# PIC.net
KiCad netlist of a schematic drawn in Altium Designer
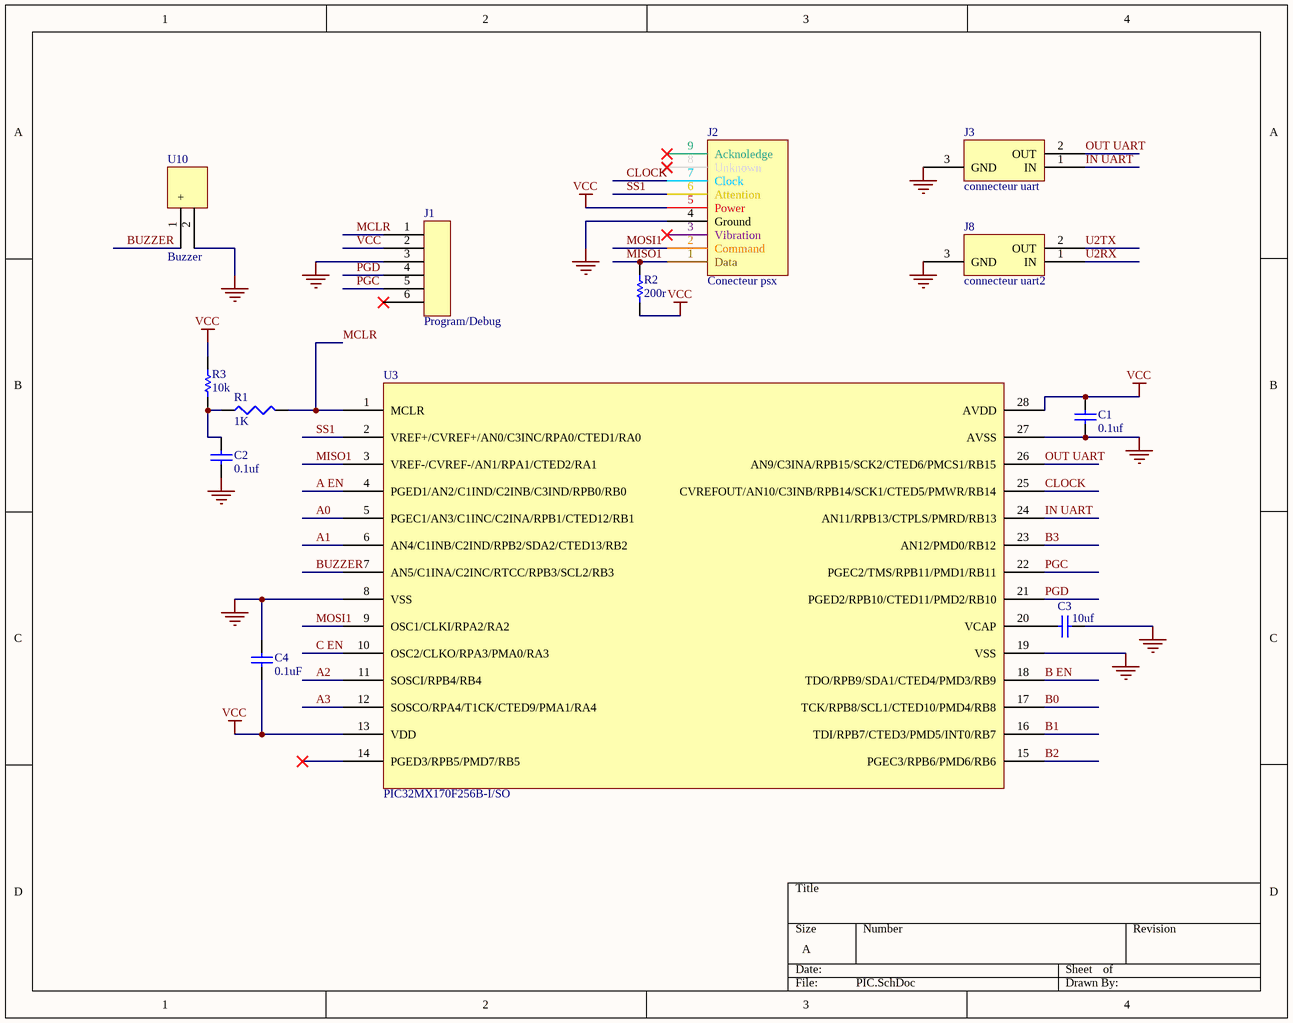
[diagram p0: PIC.SchDoc]

(export (version "E")
  (design (tool "Eeschema 10.0.6"))
  (components
    (comp (ref "C1")
      (value "0.1uf")
      (footprint "CAPC1608X09N")
      (description "Capacitor")
      (fields (field (name "PUBLISHER") "Altium Limited"))
      (libsource (lib "Miscellaneous Devices") (part "Cap"))
    )
    (comp (ref "C2")
      (value "0.1uf")
      (footprint "CAPC1608X09N")
      (description "Capacitor")
      (fields (field (name "PUBLISHER") "Altium Limited"))
      (libsource (lib "Miscellaneous Devices") (part "Cap"))
    )
    (comp (ref "C3")
      (value "10uf")
      (footprint "CAPC1608X09N")
      (description "Capacitor")
      (fields (field (name "PUBLISHER") "Altium Limited"))
      (libsource (lib "Miscellaneous Devices") (part "Cap"))
    )
    (comp (ref "C4")
      (value "0.1uF")
      (footprint "CAPC1608X09N")
      (description "Capacitor")
      (fields (field (name "PUBLISHER") "Altium Limited"))
      (libsource (lib "Miscellaneous Devices") (part "Cap"))
    )
    (comp (ref "J1")
      (value "Program/Debug")
      (footprint "Debug")
      (libsource (lib "TP-II_PD") (part "Component_1"))
    )
    (comp (ref "J2")
      (value "Conecteur psx")
      (footprint "PCBComponent_1")
      (libsource (lib "PS2_PAD") (part "Component_1"))
    )
    (comp (ref "J3")
      (value "connecteur uart")
      (footprint "uart")
      (libsource (lib "lib_protoboard") (part "connecteur uart"))
    )
    (comp (ref "J8")
      (value "connecteur uart2")
      (footprint "uart")
      (libsource (lib "lib_protoboard") (part "connecteur uart"))
    )
    (comp (ref "R1")
      (value "1K")
      (footprint "CAPC1608X09N")
      (description "Resistor")
      (fields (field (name "PUBLISHER") "Altium Limited"))
      (libsource (lib "Miscellaneous Devices") (part "Res3"))
    )
    (comp (ref "R2")
      (value "200r")
      (footprint "CAPC1608X09N")
      (description "Resistor")
      (fields (field (name "PUBLISHER") "Altium Limited"))
      (libsource (lib "Miscellaneous Devices") (part "Res1"))
    )
    (comp (ref "R3")
      (value "10k")
      (footprint "CAPC1608X09N")
      (description "Resistor")
      (fields (field (name "PUBLISHER") "Altium Limited"))
      (libsource (lib "Miscellaneous Devices") (part "Res1"))
    )
    (comp (ref "U3")
      (value "PIC32MX170F256B-I/SO")
      (footprint "SOIC127P1030X265-28N")
      (libsource (lib "lib_protoboard") (part "PICMX1XX"))
    )
    (comp (ref "U10")
      (value "Buzzer")
      (footprint "ABT-410-RC")
      (libsource (lib "lib_protoboard") (part "Buzzer"))
    )
  )
  (nets
    (net (code "1") (name "/A EN") (class "Default")
      (node (ref "U3") (pin "4") (pinfunction "PGED1/AN2/C1IND/C2INB/C3IND/RPB0/RB0_4") (pintype "power_in"))
    )
    (net (code "2") (name "/A0") (class "Default")
      (node (ref "U3") (pin "5") (pinfunction "PGEC1/AN3/C1INC/C2INA/RPB1/CTED12/RB1_5") (pintype "power_in"))
    )
    (net (code "3") (name "/A1") (class "Default")
      (node (ref "U3") (pin "6") (pinfunction "AN4/C1INB/C2IND/RPB2/SDA2/CTED13/RB2_6") (pintype "power_in"))
    )
    (net (code "4") (name "/A2") (class "Default")
      (node (ref "U3") (pin "11") (pinfunction "SOSCI/RPB4/RB4_11") (pintype "power_in"))
    )
    (net (code "5") (name "/A3") (class "Default")
      (node (ref "U3") (pin "12") (pinfunction "SOSCO/RPA4/T1CK/CTED9/PMA1/RA4_12") (pintype "power_in"))
    )
    (net (code "6") (name "/B EN") (class "Default")
      (node (ref "U3") (pin "18") (pinfunction "TDO/RPB9/SDA1/CTED4/PMD3/RB9_18") (pintype "power_in"))
    )
    (net (code "7") (name "/B0") (class "Default")
      (node (ref "U3") (pin "17") (pinfunction "TCK/RPB8/SCL1/CTED10/PMD4/RB8_17") (pintype "power_in"))
    )
    (net (code "8") (name "/B1") (class "Default")
      (node (ref "U3") (pin "16") (pinfunction "TDI/RPB7/CTED3/PMD5/INT0/RB7_16") (pintype "power_in"))
    )
    (net (code "9") (name "/B2") (class "Default")
      (node (ref "U3") (pin "15") (pinfunction "PGEC3/RPB6/PMD6/RB6_15") (pintype "power_in"))
    )
    (net (code "10") (name "/B3") (class "Default")
      (node (ref "U3") (pin "23") (pinfunction "AN12/PMD0/RB12_23") (pintype "power_in"))
    )
    (net (code "11") (name "/BUZZER") (class "Default")
      (node (ref "U10") (pin "1") (pinfunction "+_1") (pintype "passive"))
      (node (ref "U3") (pin "7") (pinfunction "AN5/C1INA/C2INC/RTCC/RPB3/SCL2/RB3_7") (pintype "power_in"))
    )
    (net (code "12") (name "/C EN") (class "Default")
      (node (ref "U3") (pin "10") (pinfunction "OSC2/CLKO/RPA3/PMA0/RA3_10") (pintype "power_in"))
    )
    (net (code "13") (name "/CLOCK") (class "Default")
      (node (ref "J2") (pin "7") (pinfunction "Clock_7") (pintype "passive"))
      (node (ref "U3") (pin "25") (pinfunction "CVREFOUT/AN10/C3INB/RPB14/SCK1/CTED5/PMWR/RB14_25") (pintype "power_in"))
    )
    (net (code "14") (name "/IN UART") (class "Default")
      (node (ref "J3") (pin "1") (pinfunction "IN_1") (pintype "passive"))
      (node (ref "U3") (pin "24") (pinfunction "AN11/RPB13/CTPLS/PMRD/RB13_24") (pintype "power_in"))
    )
    (net (code "15") (name "/MCLR") (class "Default")
      (node (ref "J1") (pin "1") (pinfunction "66_1") (pintype "passive"))
      (node (ref "R1") (pin "2") (pinfunction "2_2") (pintype "passive"))
      (node (ref "U3") (pin "1") (pinfunction "MCLR_1") (pintype "power_in"))
    )
    (net (code "16") (name "/MISO1") (class "Default")
      (node (ref "J2") (pin "1") (pinfunction "Data_1") (pintype "passive"))
      (node (ref "R2") (pin "2") (pinfunction "2_2") (pintype "passive"))
      (node (ref "U3") (pin "3") (pinfunction "VREF-/CVREF-/AN1/RPA1/CTED2/RA1_3") (pintype "power_in"))
    )
    (net (code "17") (name "/MOSI1") (class "Default")
      (node (ref "J2") (pin "2") (pinfunction "Command_2") (pintype "passive"))
      (node (ref "U3") (pin "9") (pinfunction "OSC1/CLKI/RPA2/RA2_9") (pintype "power_in"))
    )
    (net (code "18") (name "/OUT UART") (class "Default")
      (node (ref "J3") (pin "2") (pinfunction "OUT_2") (pintype "passive"))
      (node (ref "U3") (pin "26") (pinfunction "AN9/C3INA/RPB15/SCK2/CTED6/PMCS1/RB15_26") (pintype "power_in"))
    )
    (net (code "19") (name "/PGC") (class "Default")
      (node (ref "J1") (pin "5") (pinfunction "5_5") (pintype "passive"))
      (node (ref "U3") (pin "22") (pinfunction "PGEC2/TMS/RPB11/PMD1/RB11_22") (pintype "power_in"))
    )
    (net (code "20") (name "/PGD") (class "Default")
      (node (ref "J1") (pin "4") (pinfunction "4_4") (pintype "passive"))
      (node (ref "U3") (pin "21") (pinfunction "PGED2/RPB10/CTED11/PMD2/RB10_21") (pintype "power_in"))
    )
    (net (code "21") (name "/SS1") (class "Default")
      (node (ref "J2") (pin "6") (pinfunction "Attention_6") (pintype "passive"))
      (node (ref "U3") (pin "2") (pinfunction "VREF+/CVREF+/AN0/C3INC/RPA0/CTED1/RA0_2") (pintype "power_in"))
    )
    (net (code "22") (name "/U2RX") (class "Default")
      (node (ref "J8") (pin "1") (pinfunction "IN_1") (pintype "passive"))
    )
    (net (code "23") (name "/U2TX") (class "Default")
      (node (ref "J8") (pin "2") (pinfunction "OUT_2") (pintype "passive"))
    )
    (net (code "24") (name "GND") (class "Default")
      (node (ref "C1") (pin "1") (pinfunction "1_1") (pintype "passive"))
      (node (ref "C2") (pin "1") (pinfunction "1_1") (pintype "passive"))
      (node (ref "C3") (pin "2") (pinfunction "2_2") (pintype "passive"))
      (node (ref "C4") (pin "2") (pinfunction "2_2") (pintype "passive"))
      (node (ref "J1") (pin "3") (pinfunction "3_3") (pintype "passive"))
      (node (ref "J2") (pin "4") (pinfunction "Ground_4") (pintype "passive"))
      (node (ref "J3") (pin "3") (pinfunction "GND_3") (pintype "passive"))
      (node (ref "J8") (pin "3") (pinfunction "GND_3") (pintype "passive"))
      (node (ref "U10") (pin "2") (pinfunction "-_2") (pintype "passive"))
      (node (ref "U3") (pin "19") (pinfunction "VSS_19") (pintype "power_in"))
      (node (ref "U3") (pin "27") (pinfunction "AVSS_27") (pintype "power_in"))
      (node (ref "U3") (pin "8") (pinfunction "VSS_8") (pintype "power_in"))
    )
    (net (code "25") (name "Net-(C2-Pad2)") (class "Default")
      (node (ref "C2") (pin "2") (pinfunction "2_2") (pintype "passive"))
      (node (ref "R1") (pin "1") (pinfunction "1_1") (pintype "passive"))
      (node (ref "R3") (pin "1") (pinfunction "1_1") (pintype "passive"))
    )
    (net (code "26") (name "Net-(U3-VCAP)") (class "Default")
      (node (ref "C3") (pin "1") (pinfunction "1_1") (pintype "passive"))
      (node (ref "U3") (pin "20") (pinfunction "VCAP_20") (pintype "power_in"))
    )
    (net (code "27") (name "VCC") (class "Default")
      (node (ref "C1") (pin "2") (pinfunction "2_2") (pintype "passive"))
      (node (ref "C4") (pin "1") (pinfunction "1_1") (pintype "passive"))
      (node (ref "J1") (pin "2") (pinfunction "2_2") (pintype "passive"))
      (node (ref "J2") (pin "5") (pinfunction "Power_5") (pintype "passive"))
      (node (ref "R2") (pin "1") (pinfunction "1_1") (pintype "passive"))
      (node (ref "R3") (pin "2") (pinfunction "2_2") (pintype "passive"))
      (node (ref "U3") (pin "13") (pinfunction "VDD_13") (pintype "power_in"))
      (node (ref "U3") (pin "28") (pinfunction "AVDD_28") (pintype "power_in"))
    )
    (net (code "28") (name "unconnected-(J1-Pad6)") (class "Default")
      (node (ref "J1") (pin "6") (pinfunction "6_6") (pintype "passive+no_connect"))
    )
    (net (code "29") (name "unconnected-(J2-Acknoledge-Pad9)") (class "Default")
      (node (ref "J2") (pin "9") (pinfunction "Acknoledge_9") (pintype "passive+no_connect"))
    )
    (net (code "30") (name "unconnected-(J2-Unknown-Pad8)") (class "Default")
      (node (ref "J2") (pin "8") (pinfunction "Unknown_8") (pintype "passive+no_connect"))
    )
    (net (code "31") (name "unconnected-(J2-Vibration-Pad3)") (class "Default")
      (node (ref "J2") (pin "3") (pinfunction "Vibration_3") (pintype "passive+no_connect"))
    )
    (net (code "32") (name "unconnected-(U3-PGED3{slash}RPB5{slash}PMD7{slash}RB5-Pad14)") (class "Default")
      (node (ref "U3") (pin "14") (pinfunction "PGED3/RPB5/PMD7/RB5_14") (pintype "power_in+no_connect"))
    )
  )
)
